# T07_-Schematic_V4.net
KiCad netlist of a schematic drawn in EAGLE
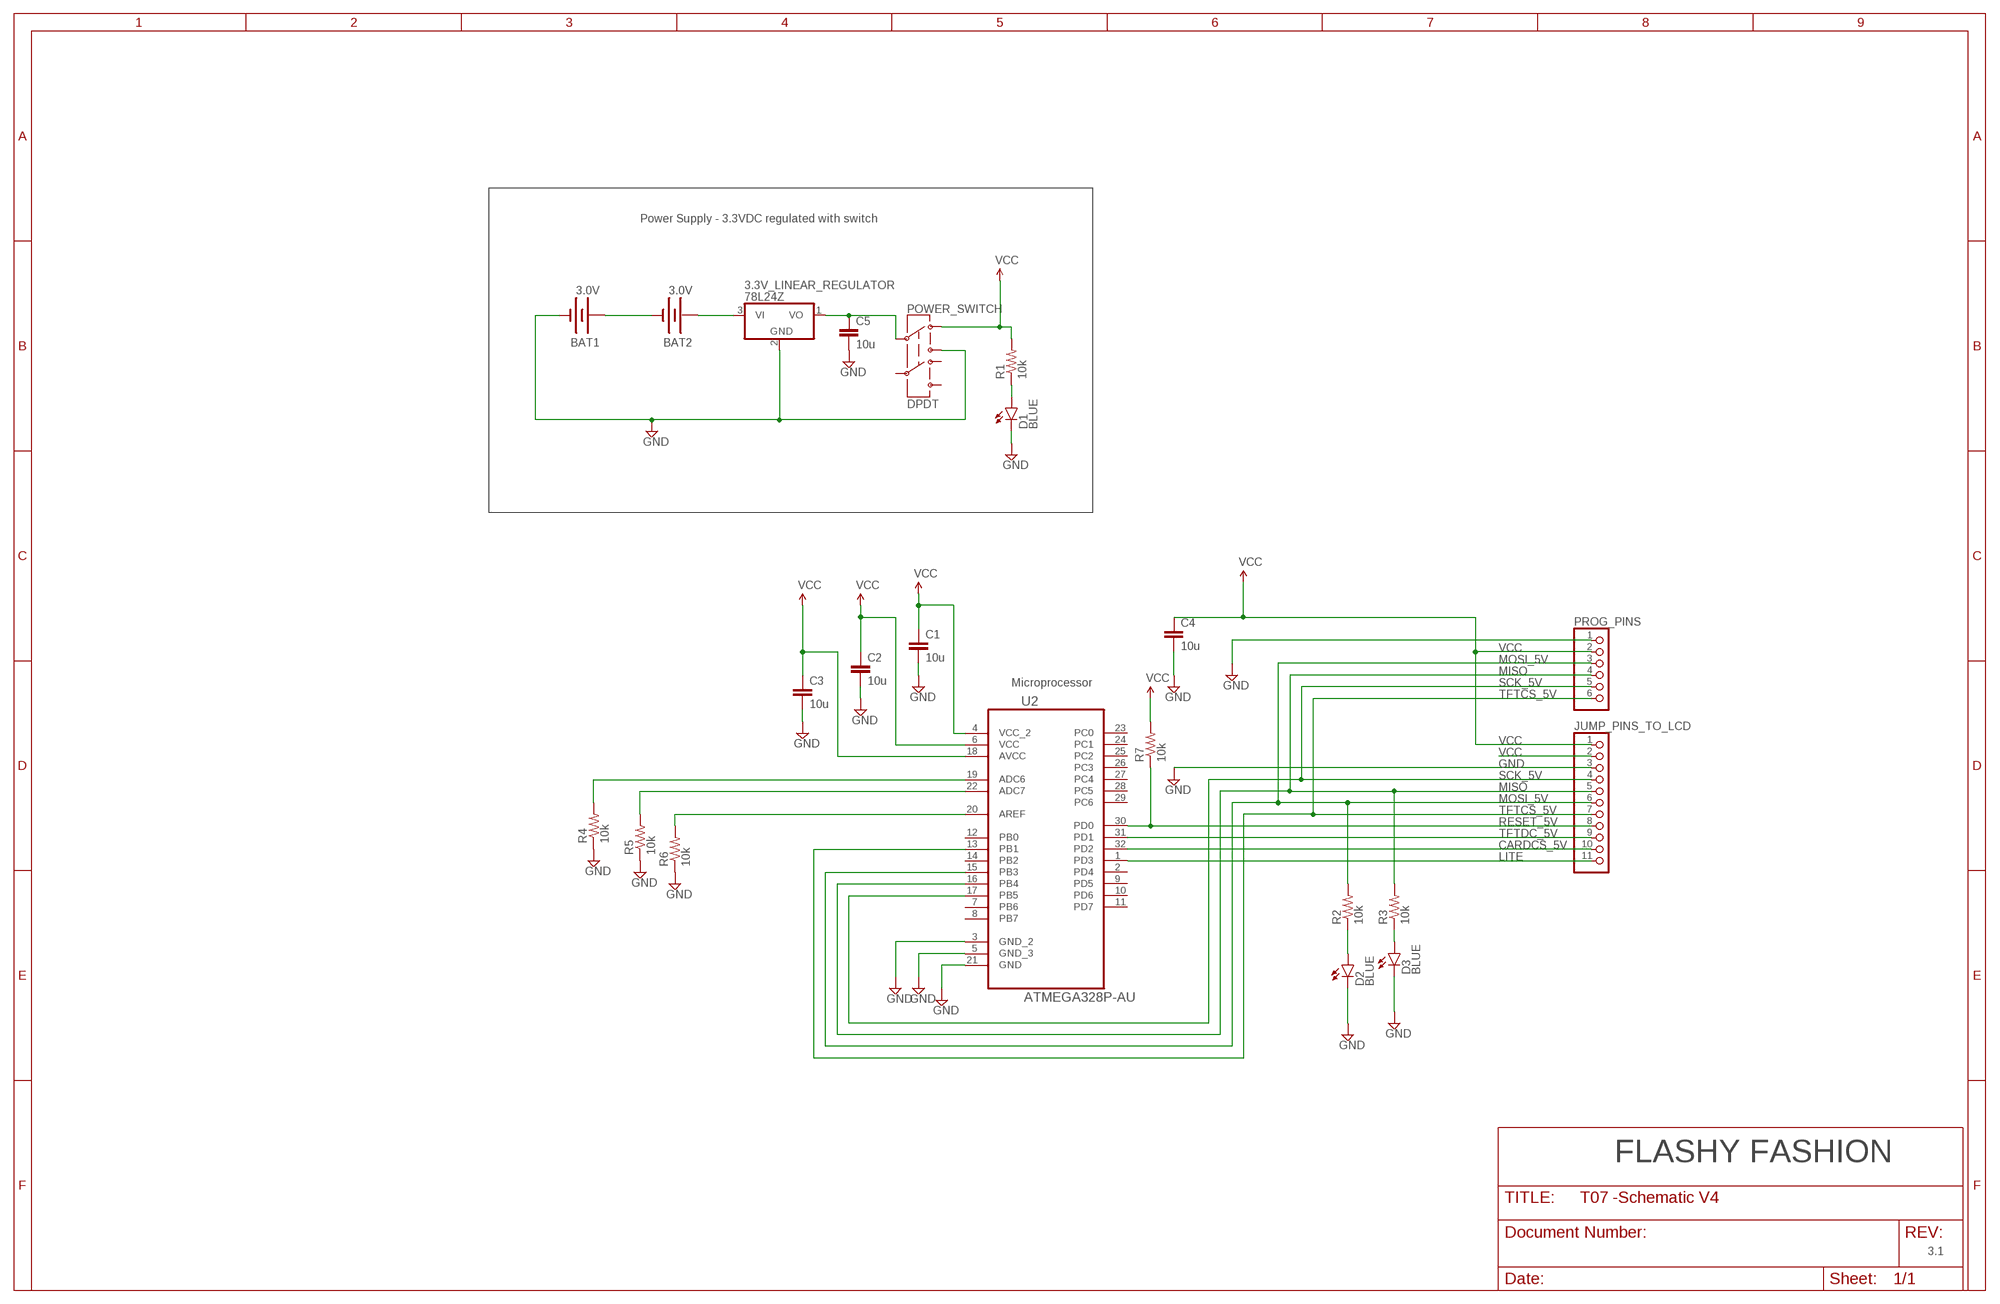
[diagram p0: schematic, sheet 1]

(export (version "E")
  (design (tool "Eeschema 10.0.6"))
  (components
    (comp (ref "3.3V_LINEAR_REGULATOR")
      (value "78L24Z")
      (footprint "eagle-import:TO92")
      (libsource (lib "eagle-import") (part "78ZL24"))
    )
    (comp (ref "BAT1")
      (value "3.0V")
      (footprint "eagle-import:BATTCON_245MM_PTH")
      (libsource (lib "eagle-import") (part "BATTERY245PTH"))
    )
    (comp (ref "BAT2")
      (value "3.0V")
      (footprint "eagle-import:BATTCON_245MM_PTH")
      (libsource (lib "eagle-import") (part "BATTERY245PTH"))
    )
    (comp (ref "C1")
      (value "10u")
      (footprint "eagle-import:1206")
      (libsource (lib "eagle-import") (part "CAP1206"))
    )
    (comp (ref "C2")
      (value "10u")
      (footprint "eagle-import:1206")
      (libsource (lib "eagle-import") (part "CAP1206"))
    )
    (comp (ref "C3")
      (value "10u")
      (footprint "eagle-import:1206")
      (libsource (lib "eagle-import") (part "CAP1206"))
    )
    (comp (ref "C4")
      (value "10u")
      (footprint "eagle-import:1206")
      (libsource (lib "eagle-import") (part "CAP1206"))
    )
    (comp (ref "C5")
      (value "10u")
      (footprint "eagle-import:1206")
      (libsource (lib "eagle-import") (part "CAP1206"))
    )
    (comp (ref "D1")
      (value "BLUE")
      (footprint "eagle-import:LED-1206")
      (libsource (lib "eagle-import") (part "LED-BLUE1206"))
    )
    (comp (ref "D2")
      (value "BLUE")
      (footprint "eagle-import:LED-1206")
      (libsource (lib "eagle-import") (part "LED-BLUE1206"))
    )
    (comp (ref "D3")
      (value "BLUE")
      (footprint "eagle-import:LED-1206")
      (libsource (lib "eagle-import") (part "LED-BLUE1206"))
    )
    (comp (ref "JUMP_PINS_TO_LCD")
      (value "HEADER-1X1176MIL")
      (footprint "eagle-import:1X11_ROUND_76")
      (libsource (lib "eagle-import") (part "HEADER-1X1176MIL"))
    )
    (comp (ref "POWER_SWITCH")
      (value "DPDT")
      (footprint "eagle-import:AYZ0202")
      (libsource (lib "eagle-import") (part "SWITCH-DPDTAYZ0202"))
    )
    (comp (ref "PROG_PINS")
      (value "PINHD-1X6-3.5MM")
      (footprint "eagle-import:1X06-3.5MM")
      (libsource (lib "eagle-import") (part "PINHD-1X6-3.5MM"))
    )
    (comp (ref "R1")
      (value "10k")
      (footprint "eagle-import:1206")
      (libsource (lib "eagle-import") (part "SparkFun-Resistors_RESISTOR1206"))
    )
    (comp (ref "R2")
      (value "10k")
      (footprint "eagle-import:1206")
      (libsource (lib "eagle-import") (part "SparkFun-Resistors_RESISTOR1206"))
    )
    (comp (ref "R3")
      (value "10k")
      (footprint "eagle-import:1206")
      (libsource (lib "eagle-import") (part "SparkFun-Resistors_RESISTOR1206"))
    )
    (comp (ref "R4")
      (value "10k")
      (footprint "eagle-import:1206")
      (libsource (lib "eagle-import") (part "SparkFun-Resistors_RESISTOR1206"))
    )
    (comp (ref "R5")
      (value "10k")
      (footprint "eagle-import:1206")
      (libsource (lib "eagle-import") (part "SparkFun-Resistors_RESISTOR1206"))
    )
    (comp (ref "R6")
      (value "10k")
      (footprint "eagle-import:1206")
      (libsource (lib "eagle-import") (part "SparkFun-Resistors_RESISTOR1206"))
    )
    (comp (ref "R7")
      (value "10k")
      (footprint "eagle-import:1206")
      (libsource (lib "eagle-import") (part "RESISTOR1206"))
    )
    (comp (ref "U2")
      (value "ATMEGA328P-AU")
      (footprint "eagle-import:QFP80P900X900X120-32N")
      (libsource (lib "eagle-import") (part "ATMEGA328P-AU"))
    )
  )
  (nets
    (net (code "1") (name "/CARDCS_5V") (class "Default")
      (node (ref "JUMP_PINS_TO_LCD") (pin "10") (pinfunction "10_10") (pintype "passive"))
      (node (ref "U2") (pin "32") (pinfunction "PD2_32") (pintype "bidirectional"))
    )
    (net (code "2") (name "/LITE") (class "Default")
      (node (ref "JUMP_PINS_TO_LCD") (pin "11") (pinfunction "11_11") (pintype "passive"))
      (node (ref "U2") (pin "1") (pinfunction "PD3_1") (pintype "bidirectional"))
    )
    (net (code "3") (name "/MISO") (class "Default")
      (node (ref "JUMP_PINS_TO_LCD") (pin "5") (pinfunction "5_5") (pintype "passive"))
      (node (ref "PROG_PINS") (pin "4") (pinfunction "4_4") (pintype "passive"))
      (node (ref "R3") (pin "2") (pinfunction "2_2") (pintype "passive"))
      (node (ref "U2") (pin "16") (pinfunction "PB4_16") (pintype "bidirectional"))
    )
    (net (code "4") (name "/MOSI_5V") (class "Default")
      (node (ref "JUMP_PINS_TO_LCD") (pin "6") (pinfunction "6_6") (pintype "passive"))
      (node (ref "PROG_PINS") (pin "3") (pinfunction "3_3") (pintype "passive"))
      (node (ref "R2") (pin "2") (pinfunction "2_2") (pintype "passive"))
      (node (ref "U2") (pin "15") (pinfunction "PB3_15") (pintype "bidirectional"))
    )
    (net (code "5") (name "/RESET_5V") (class "Default")
      (node (ref "JUMP_PINS_TO_LCD") (pin "8") (pinfunction "8_8") (pintype "passive"))
      (node (ref "R7") (pin "1") (pinfunction "1_1") (pintype "passive"))
      (node (ref "U2") (pin "30") (pinfunction "PD0_30") (pintype "bidirectional"))
    )
    (net (code "6") (name "/SCK_5V") (class "Default")
      (node (ref "JUMP_PINS_TO_LCD") (pin "4") (pinfunction "4_4") (pintype "passive"))
      (node (ref "PROG_PINS") (pin "5") (pinfunction "5_5") (pintype "passive"))
      (node (ref "U2") (pin "17") (pinfunction "PB5_17") (pintype "bidirectional"))
    )
    (net (code "7") (name "/TFTCS_5V") (class "Default")
      (node (ref "JUMP_PINS_TO_LCD") (pin "7") (pinfunction "7_7") (pintype "passive"))
      (node (ref "PROG_PINS") (pin "6") (pinfunction "6_6") (pintype "passive"))
      (node (ref "U2") (pin "13") (pinfunction "PB1_13") (pintype "bidirectional"))
    )
    (net (code "8") (name "/TFTDC_5V") (class "Default")
      (node (ref "JUMP_PINS_TO_LCD") (pin "9") (pinfunction "9_9") (pintype "passive"))
      (node (ref "U2") (pin "31") (pinfunction "PD1_31") (pintype "bidirectional"))
    )
    (net (code "9") (name "GND") (class "Default")
      (node (ref "3.3V_LINEAR_REGULATOR") (pin "2") (pinfunction "GND_2") (pintype "passive"))
      (node (ref "BAT1") (pin "2") (pinfunction "-_2") (pintype "power_in"))
      (node (ref "C1") (pin "2") (pinfunction "2_2") (pintype "passive"))
      (node (ref "C2") (pin "2") (pinfunction "2_2") (pintype "passive"))
      (node (ref "C3") (pin "2") (pinfunction "2_2") (pintype "passive"))
      (node (ref "C4") (pin "2") (pinfunction "2_2") (pintype "passive"))
      (node (ref "C5") (pin "2") (pinfunction "2_2") (pintype "passive"))
      (node (ref "D1") (pin "C") (pinfunction "C_C") (pintype "passive"))
      (node (ref "D2") (pin "C") (pinfunction "C_C") (pintype "passive"))
      (node (ref "D3") (pin "C") (pinfunction "C_C") (pintype "passive"))
      (node (ref "JUMP_PINS_TO_LCD") (pin "3") (pinfunction "3_3") (pintype "passive"))
      (node (ref "POWER_SWITCH") (pin "3") (pinfunction "3_3") (pintype "bidirectional"))
      (node (ref "PROG_PINS") (pin "1") (pinfunction "1_1") (pintype "passive"))
      (node (ref "R4") (pin "1") (pinfunction "1_1") (pintype "passive"))
      (node (ref "R5") (pin "1") (pinfunction "1_1") (pintype "passive"))
      (node (ref "R6") (pin "1") (pinfunction "1_1") (pintype "passive"))
      (node (ref "U2") (pin "21") (pinfunction "GND_21") (pintype "passive"))
      (node (ref "U2") (pin "3") (pinfunction "GND_2_3") (pintype "passive"))
      (node (ref "U2") (pin "5") (pinfunction "GND_3_5") (pintype "passive"))
    )
    (net (code "10") (name "Net-(3.3V_LINEAR_REGULATOR-VI)") (class "Default")
      (node (ref "3.3V_LINEAR_REGULATOR") (pin "3") (pinfunction "VI_3") (pintype "input"))
      (node (ref "BAT2") (pin "3") (pinfunction "+_3") (pintype "power_in"))
    )
    (net (code "11") (name "Net-(3.3V_LINEAR_REGULATOR-VO)") (class "Default")
      (node (ref "3.3V_LINEAR_REGULATOR") (pin "1") (pinfunction "VO_1") (pintype "passive"))
      (node (ref "C5") (pin "1") (pinfunction "1_1") (pintype "passive"))
      (node (ref "POWER_SWITCH") (pin "2") (pinfunction "2_2") (pintype "bidirectional"))
    )
    (net (code "12") (name "Net-(BAT1-+)") (class "Default")
      (node (ref "BAT1") (pin "3") (pinfunction "+_3") (pintype "power_in"))
      (node (ref "BAT2") (pin "2") (pinfunction "-_2") (pintype "power_in"))
    )
    (net (code "13") (name "Net-(D1-PadA)") (class "Default")
      (node (ref "D1") (pin "A") (pinfunction "A_A") (pintype "passive"))
      (node (ref "R1") (pin "1") (pinfunction "1_1") (pintype "passive"))
    )
    (net (code "14") (name "Net-(D2-PadA)") (class "Default")
      (node (ref "D2") (pin "A") (pinfunction "A_A") (pintype "passive"))
      (node (ref "R2") (pin "1") (pinfunction "1_1") (pintype "passive"))
    )
    (net (code "15") (name "Net-(D3-PadA)") (class "Default")
      (node (ref "D3") (pin "A") (pinfunction "A_A") (pintype "passive"))
      (node (ref "R3") (pin "1") (pinfunction "1_1") (pintype "passive"))
    )
    (net (code "16") (name "Net-(U2-ADC6)") (class "Default")
      (node (ref "R4") (pin "2") (pinfunction "2_2") (pintype "passive"))
      (node (ref "U2") (pin "19") (pinfunction "ADC6_19") (pintype "input"))
    )
    (net (code "17") (name "Net-(U2-ADC7)") (class "Default")
      (node (ref "R5") (pin "2") (pinfunction "2_2") (pintype "passive"))
      (node (ref "U2") (pin "22") (pinfunction "ADC7_22") (pintype "input"))
    )
    (net (code "18") (name "Net-(U2-AREF)") (class "Default")
      (node (ref "R6") (pin "2") (pinfunction "2_2") (pintype "passive"))
      (node (ref "U2") (pin "20") (pinfunction "AREF_20") (pintype "input"))
    )
    (net (code "19") (name "VCC") (class "Default")
      (node (ref "C1") (pin "1") (pinfunction "1_1") (pintype "passive"))
      (node (ref "C2") (pin "1") (pinfunction "1_1") (pintype "passive"))
      (node (ref "C3") (pin "1") (pinfunction "1_1") (pintype "passive"))
      (node (ref "C4") (pin "1") (pinfunction "1_1") (pintype "passive"))
      (node (ref "JUMP_PINS_TO_LCD") (pin "1") (pinfunction "1_1") (pintype "passive"))
      (node (ref "POWER_SWITCH") (pin "1") (pinfunction "1_1") (pintype "bidirectional"))
      (node (ref "PROG_PINS") (pin "2") (pinfunction "2_2") (pintype "passive"))
      (node (ref "R1") (pin "2") (pinfunction "2_2") (pintype "passive"))
      (node (ref "R7") (pin "2") (pinfunction "2_2") (pintype "passive"))
      (node (ref "U2") (pin "18") (pinfunction "AVCC_18") (pintype "power_in"))
      (node (ref "U2") (pin "4") (pinfunction "VCC_2_4") (pintype "power_in"))
      (node (ref "U2") (pin "6") (pinfunction "VCC_6") (pintype "power_in"))
    )
    (net (code "20") (name "unconnected-(JUMP_PINS_TO_LCD-Pad2)") (class "Default")
      (node (ref "JUMP_PINS_TO_LCD") (pin "2") (pinfunction "2_2") (pintype "passive"))
    )
    (net (code "21") (name "unconnected-(POWER_SWITCH-Pad4)") (class "Default")
      (node (ref "POWER_SWITCH") (pin "4") (pinfunction "4_4") (pintype "bidirectional"))
    )
    (net (code "22") (name "unconnected-(POWER_SWITCH-Pad5)") (class "Default")
      (node (ref "POWER_SWITCH") (pin "5") (pinfunction "5_5") (pintype "bidirectional"))
    )
    (net (code "23") (name "unconnected-(POWER_SWITCH-Pad6)") (class "Default")
      (node (ref "POWER_SWITCH") (pin "6") (pinfunction "6_6") (pintype "bidirectional"))
    )
    (net (code "24") (name "unconnected-(U2-PB0-Pad12)") (class "Default")
      (node (ref "U2") (pin "12") (pinfunction "PB0_12") (pintype "bidirectional"))
    )
    (net (code "25") (name "unconnected-(U2-PB2-Pad14)") (class "Default")
      (node (ref "U2") (pin "14") (pinfunction "PB2_14") (pintype "bidirectional"))
    )
    (net (code "26") (name "unconnected-(U2-PB6-Pad7)") (class "Default")
      (node (ref "U2") (pin "7") (pinfunction "PB6_7") (pintype "bidirectional"))
    )
    (net (code "27") (name "unconnected-(U2-PB7-Pad8)") (class "Default")
      (node (ref "U2") (pin "8") (pinfunction "PB7_8") (pintype "bidirectional"))
    )
    (net (code "28") (name "unconnected-(U2-PC0-Pad23)") (class "Default")
      (node (ref "U2") (pin "23") (pinfunction "PC0_23") (pintype "bidirectional"))
    )
    (net (code "29") (name "unconnected-(U2-PC1-Pad24)") (class "Default")
      (node (ref "U2") (pin "24") (pinfunction "PC1_24") (pintype "bidirectional"))
    )
    (net (code "30") (name "unconnected-(U2-PC2-Pad25)") (class "Default")
      (node (ref "U2") (pin "25") (pinfunction "PC2_25") (pintype "bidirectional"))
    )
    (net (code "31") (name "unconnected-(U2-PC3-Pad26)") (class "Default")
      (node (ref "U2") (pin "26") (pinfunction "PC3_26") (pintype "bidirectional"))
    )
    (net (code "32") (name "unconnected-(U2-PC4-Pad27)") (class "Default")
      (node (ref "U2") (pin "27") (pinfunction "PC4_27") (pintype "bidirectional"))
    )
    (net (code "33") (name "unconnected-(U2-PC5-Pad28)") (class "Default")
      (node (ref "U2") (pin "28") (pinfunction "PC5_28") (pintype "bidirectional"))
    )
    (net (code "34") (name "unconnected-(U2-PC6-Pad29)") (class "Default")
      (node (ref "U2") (pin "29") (pinfunction "PC6_29") (pintype "bidirectional"))
    )
    (net (code "35") (name "unconnected-(U2-PD4-Pad2)") (class "Default")
      (node (ref "U2") (pin "2") (pinfunction "PD4_2") (pintype "bidirectional"))
    )
    (net (code "36") (name "unconnected-(U2-PD5-Pad9)") (class "Default")
      (node (ref "U2") (pin "9") (pinfunction "PD5_9") (pintype "bidirectional"))
    )
    (net (code "37") (name "unconnected-(U2-PD6-Pad10)") (class "Default")
      (node (ref "U2") (pin "10") (pinfunction "PD6_10") (pintype "bidirectional"))
    )
    (net (code "38") (name "unconnected-(U2-PD7-Pad11)") (class "Default")
      (node (ref "U2") (pin "11") (pinfunction "PD7_11") (pintype "bidirectional"))
    )
  )
)
